# Bank_12_14_35.net
KiCad netlist of a schematic drawn in Altium Designer
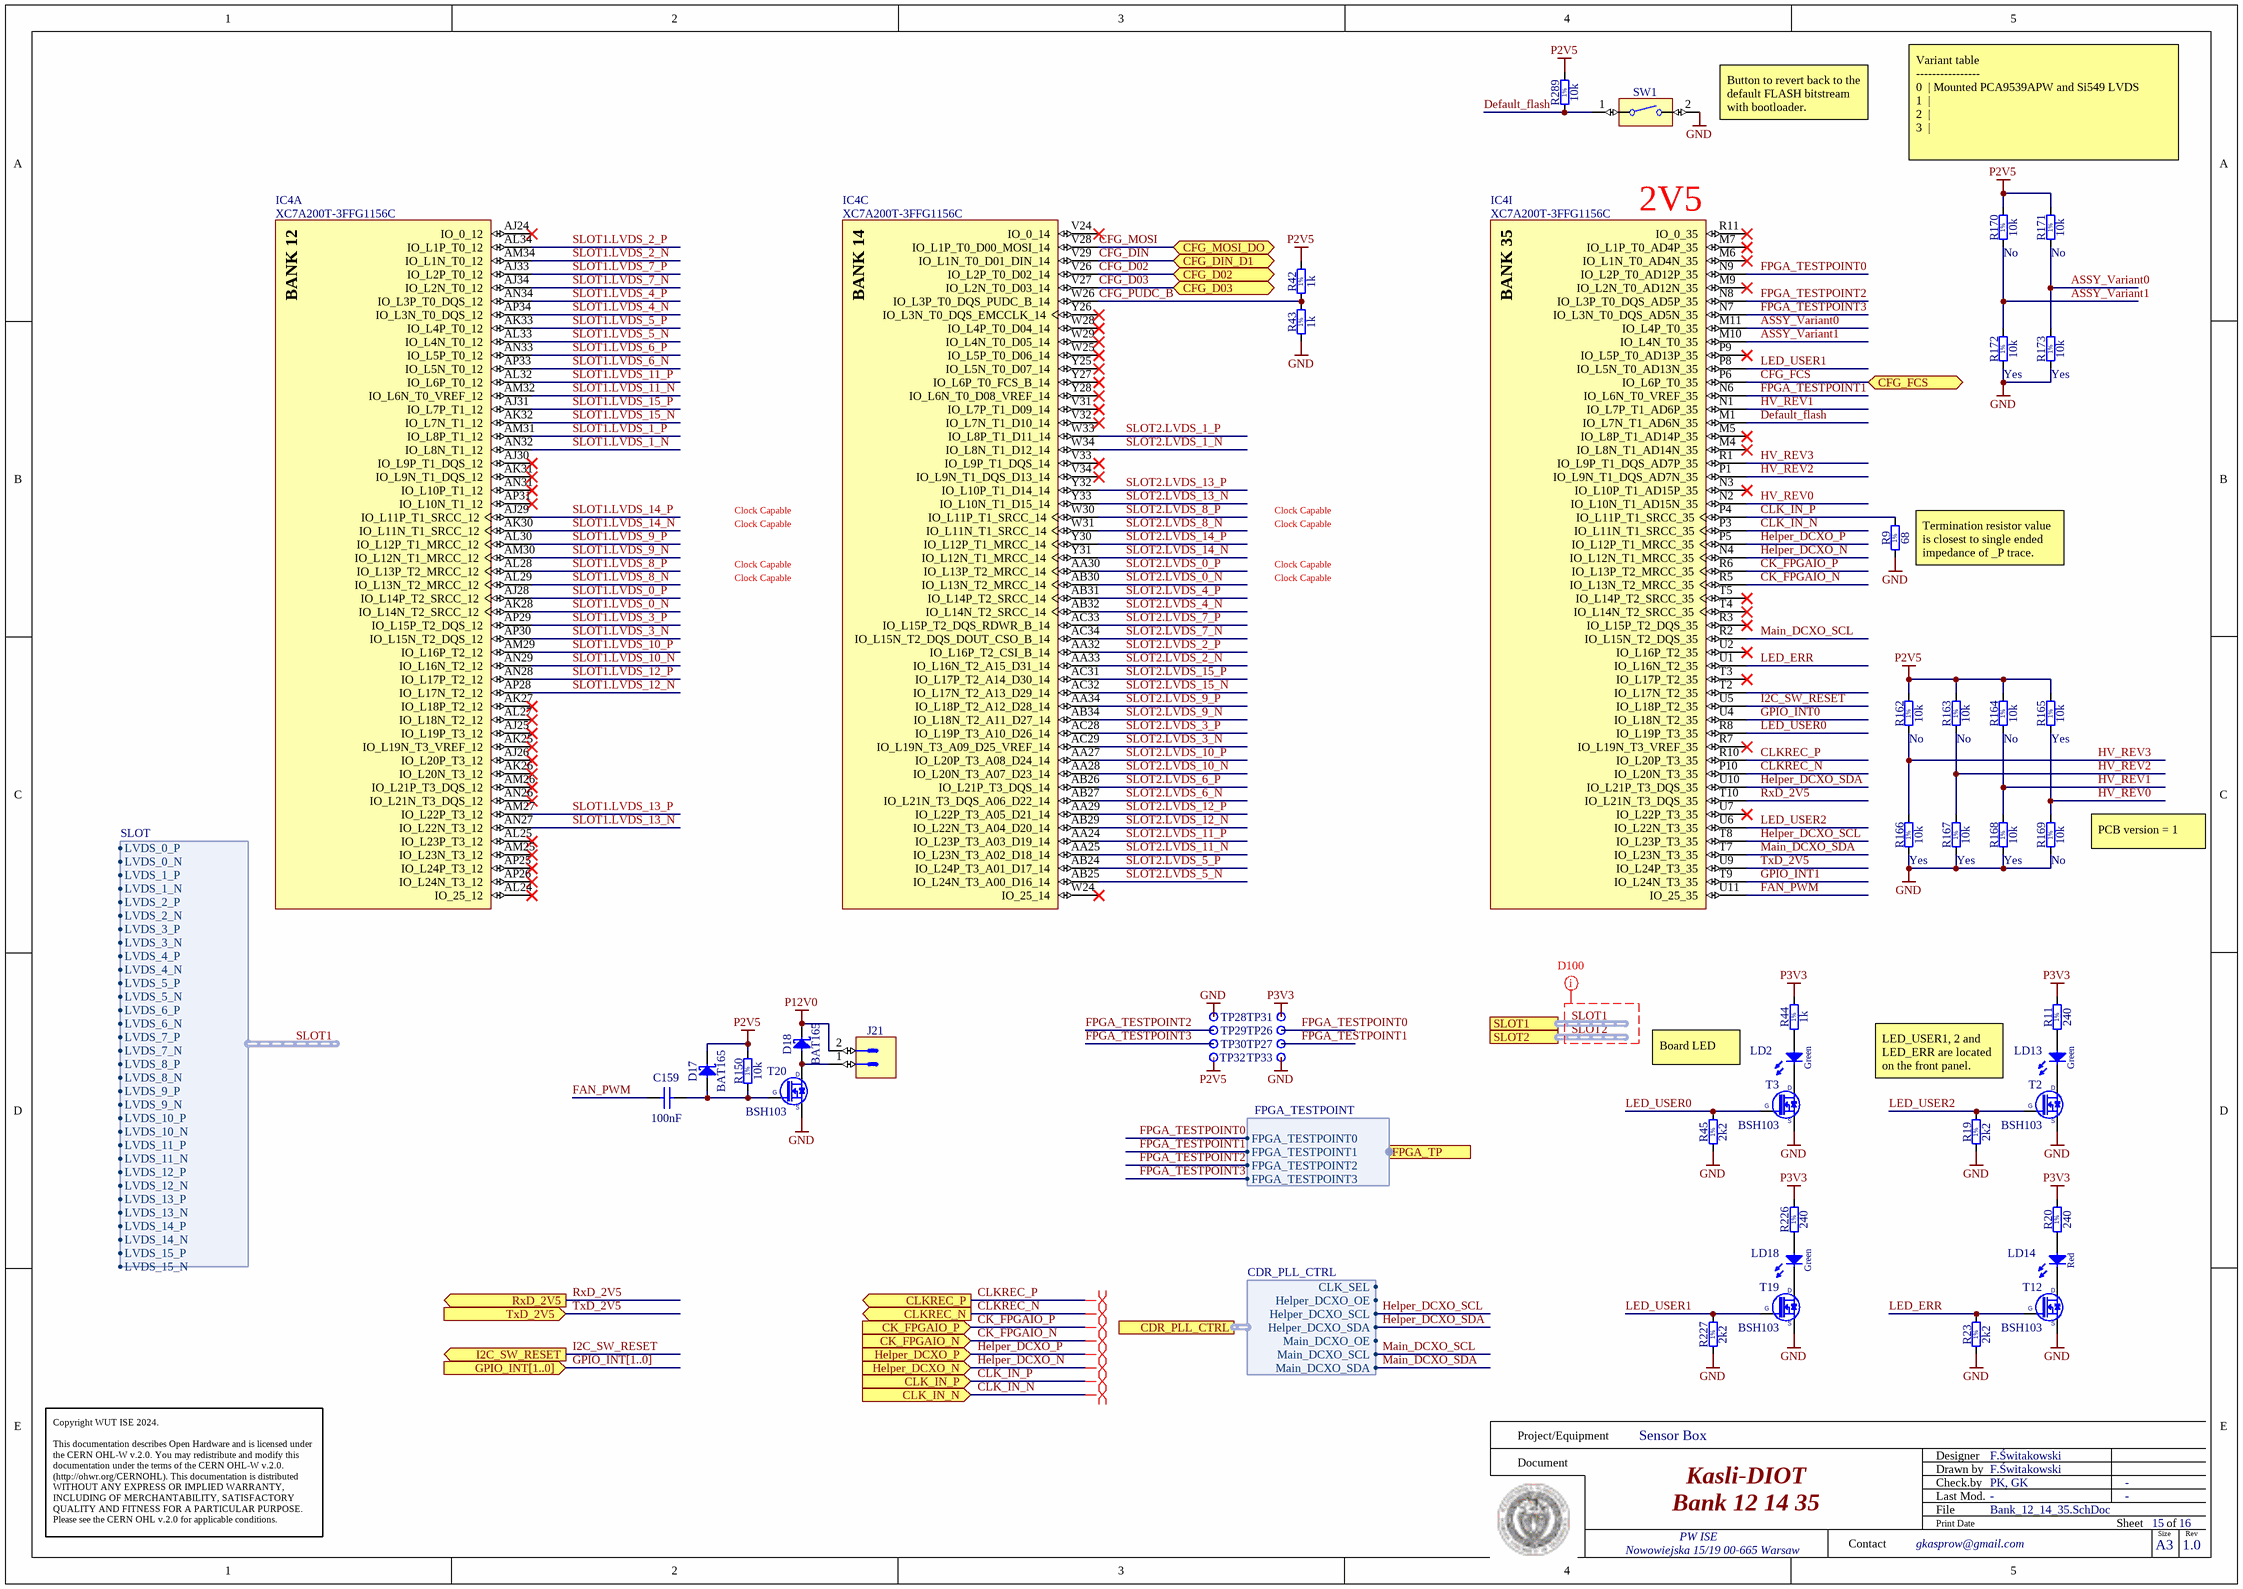
[diagram p0: Bank_12_14_35.SchDoc]

(export (version "E")
  (design (tool "Eeschema 10.0.6"))
  (components
    (comp (ref "C159")
      (value "100nF")
      (footprint "CAPC0603X33N")
      (description "Non-polarised capacitor")
      (fields
        (field (name "PART NUMBER") "CC0201_100NF_6.3V_10%_X5R")
        (field (name "VOLTAGE") "6.3V")
        (field (name "AUTHOR") "CERN DEM JLC")
      )
      (libsource (lib "Capacitors") (part "Capacitor - non polarized"))
    )
    (comp (ref "D17")
      (value "BAT165")
      (footprint "SOD2512X110N")
      (description "Schottky Diode")
      (fields
        (field (name "VOLTAGE") "40V")
        (field (name "POWER") "750mA")
        (field (name "AUTHOR") "CERN DEM JLC")
      )
      (libsource (lib "ICs And Semiconductors") (part "Diode Schottky"))
    )
    (comp (ref "D18")
      (value "BAT165")
      (footprint "SOD2512X110N")
      (description "Schottky Diode")
      (fields
        (field (name "VOLTAGE") "40V")
        (field (name "POWER") "750mA")
        (field (name "AUTHOR") "CERN DEM JLC")
      )
      (libsource (lib "ICs And Semiconductors") (part "Diode Schottky"))
    )
    (comp (ref "IC4")
      (value "XC7A200T-3FFG1156C")
      (footprint "BGA1156C100P34X34_3500X3500X310")
      (description "Artix-7 FPGA, 500 User I/Os, 16 GTP, 1156-Ball BGA, , Speed Grade 3, Commercial Grade, Pb-Free")
      (fields (field (name "MANUFACTURER") "XILINX") (field (name "AUTHOR") "CERN DEM JLC"))
      (libsource (lib "ICs And Semiconductors") (part "XC7A200T-3FFG1156C"))
    )
    (comp (ref "J21")
      (value "KK®")
      (footprint "MOLEX_22-27-2021")
      (description "Connector 2 Male")
      (fields
        (field (name "PART NUMBER") "MOLEX_22-27-2021")
        (field (name "MANUFACTURER") "MOLEX")
        (field (name "AUTHOR") "CERN DEM JLC")
      )
      (libsource (lib "Connectors") (part "Connector 2 Male"))
    )
    (comp (ref "LD2")
      (value "Green")
      (footprint "LED_KINGBRIGHT_KPH-1608CGCK")
      (description "LED Green 1C 2A")
      (fields
        (field (name "MANUFACTURER PART NUMBER") "KPH-1608CGCK")
        (field (name "PART NUMBER") "LED_KINGBRIGHT_KPH-1608CGCK")
        (field (name "AUTHOR") "CERN DEM JLC")
      )
      (libsource (lib "ICs And Semiconductors") (part "LED Green 1C 2A"))
    )
    (comp (ref "LD13")
      (value "Green")
      (footprint "LED_AVAGO_HSME-C120")
      (description "LED Green 1C 2A")
      (fields
        (field (name "MANUFACTURER PART NUMBER") "HSME-C120")
        (field (name "PART NUMBER") "LED_AVAGO_HSME-C120")
        (field (name "AUTHOR") "CERN DEM JMW")
      )
      (libsource (lib "ICs And Semiconductors") (part "LED Green 1C 2A"))
    )
    (comp (ref "LD14")
      (value "Red")
      (footprint "LED_AVAGO_HSMC-C120")
      (description "LED Red 1C 2A")
      (fields
        (field (name "MANUFACTURER PART NUMBER") "HSMC-C120")
        (field (name "PART NUMBER") "LED_AVAGO_HSMC-C120")
        (field (name "AUTHOR") "CERN DEM JMW")
      )
      (libsource (lib "ICs And Semiconductors") (part "LED Red 1C 2A"))
    )
    (comp (ref "LD18")
      (value "Green")
      (footprint "LED_AVAGO_HSME-C120")
      (description "LED Green 1C 2A")
      (fields
        (field (name "MANUFACTURER PART NUMBER") "HSME-C120")
        (field (name "PART NUMBER") "LED_AVAGO_HSME-C120")
        (field (name "AUTHOR") "CERN DEM JMW")
      )
      (libsource (lib "ICs And Semiconductors") (part "LED Green 1C 2A"))
    )
    (comp (ref "R9")
      (value "68")
      (footprint "RESC1005X40N")
      (description "Resistor - 1%")
      (fields
        (field (name "PART NUMBER") "R0402_68R_1%_0.0625W_100PPM")
        (field (name "POWER") "0.0625W")
        (field (name "AUTHOR") "CERN DEM JLC")
      )
      (libsource (lib "Resistors") (part "Resistor - 1%"))
    )
    (comp (ref "R11")
      (value "240")
      (footprint "RESC1005X40N")
      (description "Resistor - 1%")
      (fields
        (field (name "PART NUMBER") "R0402_240R_1%_0.0625W_100PPM")
        (field (name "POWER") "0.0625W")
        (field (name "AUTHOR") "CERN DEM JLC")
      )
      (libsource (lib "Resistors") (part "Resistor - 1%"))
    )
    (comp (ref "R19")
      (value "2k2")
      (footprint "RESC1005X40N")
      (description "Resistor - 1%")
      (fields
        (field (name "PART NUMBER") "R0402_2K2_1%_0.0625W_100PPM")
        (field (name "POWER") "0.0625W")
        (field (name "AUTHOR") "CERN DEM JLC")
      )
      (libsource (lib "Resistors") (part "Resistor - 1%"))
    )
    (comp (ref "R20")
      (value "240")
      (footprint "RESC1005X40N")
      (description "Resistor - 1%")
      (fields
        (field (name "PART NUMBER") "R0402_240R_1%_0.0625W_100PPM")
        (field (name "POWER") "0.0625W")
        (field (name "AUTHOR") "CERN DEM JLC")
      )
      (libsource (lib "Resistors") (part "Resistor - 1%"))
    )
    (comp (ref "R23")
      (value "2k2")
      (footprint "RESC1005X40N")
      (description "Resistor - 1%")
      (fields
        (field (name "PART NUMBER") "R0402_2K2_1%_0.0625W_100PPM")
        (field (name "POWER") "0.0625W")
        (field (name "AUTHOR") "CERN DEM JLC")
      )
      (libsource (lib "Resistors") (part "Resistor - 1%"))
    )
    (comp (ref "R42")
      (value "1k")
      (footprint "RESC1005X40N")
      (description "Resistor - 1%")
      (fields
        (field (name "PART NUMBER") "R0402_1K_1%_0.0625W_100PPM")
        (field (name "POWER") "0.0625W")
        (field (name "AUTHOR") "CERN DEM JLC")
      )
      (libsource (lib "Resistors") (part "Resistor - 1%"))
    )
    (comp (ref "R43")
      (value "1k")
      (footprint "RESC1005X40N")
      (description "Resistor - 1%")
      (fields
        (field (name "PART NUMBER") "R0402_1K_1%_0.0625W_100PPM")
        (field (name "POWER") "0.0625W")
        (field (name "AUTHOR") "CERN DEM JLC")
      )
      (libsource (lib "Resistors") (part "Resistor - 1%"))
    )
    (comp (ref "R44")
      (value "1k")
      (footprint "RESC1005X40N")
      (description "Resistor - 1%")
      (fields
        (field (name "PART NUMBER") "R0402_1K_1%_0.0625W_100PPM")
        (field (name "POWER") "0.0625W")
        (field (name "AUTHOR") "CERN DEM JLC")
      )
      (libsource (lib "Resistors") (part "Resistor - 1%"))
    )
    (comp (ref "R45")
      (value "2k2")
      (footprint "RESC1005X40N")
      (description "Resistor - 1%")
      (fields
        (field (name "PART NUMBER") "R0402_2K2_1%_0.0625W_100PPM")
        (field (name "POWER") "0.0625W")
        (field (name "AUTHOR") "CERN DEM JLC")
      )
      (libsource (lib "Resistors") (part "Resistor - 1%"))
    )
    (comp (ref "R150")
      (value "10k")
      (footprint "RESC1005X40N")
      (description "Resistor - 1%")
      (fields
        (field (name "PART NUMBER") "R0402_10K_1%_0.0625W_100PPM")
        (field (name "POWER") "0.0625W")
        (field (name "AUTHOR") "CERN DEM JLC")
      )
      (libsource (lib "Resistors") (part "Resistor - 1%"))
    )
    (comp (ref "R162")
      (value "10k")
      (footprint "RESC1005X40N")
      (description "Resistor - 1%")
      (fields
        (field (name "PART NUMBER") "R0402_10K_1%_0.0625W_100PPM")
        (field (name "POWER") "0.0625W")
        (field (name "MOUNTED") "No")
        (field (name "AUTHOR") "CERN DEM JLC")
      )
      (libsource (lib "Resistors") (part "Resistor - 1%"))
    )
    (comp (ref "R163")
      (value "10k")
      (footprint "RESC1005X40N")
      (description "Resistor - 1%")
      (fields
        (field (name "PART NUMBER") "R0402_10K_1%_0.0625W_100PPM")
        (field (name "POWER") "0.0625W")
        (field (name "MOUNTED") "No")
        (field (name "AUTHOR") "CERN DEM JLC")
      )
      (libsource (lib "Resistors") (part "Resistor - 1%"))
    )
    (comp (ref "R164")
      (value "10k")
      (footprint "RESC1005X40N")
      (description "Resistor - 1%")
      (fields
        (field (name "PART NUMBER") "R0402_10K_1%_0.0625W_100PPM")
        (field (name "POWER") "0.0625W")
        (field (name "MOUNTED") "No")
        (field (name "AUTHOR") "CERN DEM JLC")
      )
      (libsource (lib "Resistors") (part "Resistor - 1%"))
    )
    (comp (ref "R165")
      (value "10k")
      (footprint "RESC1005X40N")
      (description "Resistor - 1%")
      (fields
        (field (name "PART NUMBER") "R0402_10K_1%_0.0625W_100PPM")
        (field (name "POWER") "0.0625W")
        (field (name "MOUNTED") "Yes")
        (field (name "AUTHOR") "CERN DEM JLC")
      )
      (libsource (lib "Resistors") (part "Resistor - 1%"))
    )
    (comp (ref "R166")
      (value "10k")
      (footprint "RESC1005X40N")
      (description "Resistor - 1%")
      (fields
        (field (name "PART NUMBER") "R0402_10K_1%_0.0625W_100PPM")
        (field (name "POWER") "0.0625W")
        (field (name "MOUNTED") "Yes")
        (field (name "AUTHOR") "CERN DEM JLC")
      )
      (libsource (lib "Resistors") (part "Resistor - 1%"))
    )
    (comp (ref "R167")
      (value "10k")
      (footprint "RESC1005X40N")
      (description "Resistor - 1%")
      (fields
        (field (name "PART NUMBER") "R0402_10K_1%_0.0625W_100PPM")
        (field (name "POWER") "0.0625W")
        (field (name "MOUNTED") "Yes")
        (field (name "AUTHOR") "CERN DEM JLC")
      )
      (libsource (lib "Resistors") (part "Resistor - 1%"))
    )
    (comp (ref "R168")
      (value "10k")
      (footprint "RESC1005X40N")
      (description "Resistor - 1%")
      (fields
        (field (name "PART NUMBER") "R0402_10K_1%_0.0625W_100PPM")
        (field (name "POWER") "0.0625W")
        (field (name "MOUNTED") "Yes")
        (field (name "AUTHOR") "CERN DEM JLC")
      )
      (libsource (lib "Resistors") (part "Resistor - 1%"))
    )
    (comp (ref "R169")
      (value "10k")
      (footprint "RESC1005X40N")
      (description "Resistor - 1%")
      (fields
        (field (name "PART NUMBER") "R0402_10K_1%_0.0625W_100PPM")
        (field (name "POWER") "0.0625W")
        (field (name "MOUNTED") "No")
        (field (name "AUTHOR") "CERN DEM JLC")
      )
      (libsource (lib "Resistors") (part "Resistor - 1%"))
    )
    (comp (ref "R170")
      (value "10k")
      (footprint "RESC1005X40N")
      (description "Resistor - 1%")
      (fields
        (field (name "PART NUMBER") "R0402_10K_1%_0.0625W_100PPM")
        (field (name "POWER") "0.0625W")
        (field (name "MOUNTED") "No")
        (field (name "AUTHOR") "CERN DEM JLC")
      )
      (libsource (lib "Resistors") (part "Resistor - 1%"))
    )
    (comp (ref "R171")
      (value "10k")
      (footprint "RESC1005X40N")
      (description "Resistor - 1%")
      (fields
        (field (name "PART NUMBER") "R0402_10K_1%_0.0625W_100PPM")
        (field (name "POWER") "0.0625W")
        (field (name "MOUNTED") "No")
        (field (name "AUTHOR") "CERN DEM JLC")
      )
      (libsource (lib "Resistors") (part "Resistor - 1%"))
    )
    (comp (ref "R172")
      (value "10k")
      (footprint "RESC1005X40N")
      (description "Resistor - 1%")
      (fields
        (field (name "PART NUMBER") "R0402_10K_1%_0.0625W_100PPM")
        (field (name "POWER") "0.0625W")
        (field (name "MOUNTED") "Yes")
        (field (name "AUTHOR") "CERN DEM JLC")
      )
      (libsource (lib "Resistors") (part "Resistor - 1%"))
    )
    (comp (ref "R173")
      (value "10k")
      (footprint "RESC1005X40N")
      (description "Resistor - 1%")
      (fields
        (field (name "PART NUMBER") "R0402_10K_1%_0.0625W_100PPM")
        (field (name "POWER") "0.0625W")
        (field (name "MOUNTED") "Yes")
        (field (name "AUTHOR") "CERN DEM JLC")
      )
      (libsource (lib "Resistors") (part "Resistor - 1%"))
    )
    (comp (ref "R226")
      (value "240")
      (footprint "RESC1005X40N")
      (description "Resistor - 1%")
      (fields
        (field (name "PART NUMBER") "R0402_240R_1%_0.0625W_100PPM")
        (field (name "POWER") "0.0625W")
        (field (name "AUTHOR") "CERN DEM JLC")
      )
      (libsource (lib "Resistors") (part "Resistor - 1%"))
    )
    (comp (ref "R227")
      (value "2k2")
      (footprint "RESC1005X40N")
      (description "Resistor - 1%")
      (fields
        (field (name "PART NUMBER") "R0402_2K2_1%_0.0625W_100PPM")
        (field (name "POWER") "0.0625W")
        (field (name "AUTHOR") "CERN DEM JLC")
      )
      (libsource (lib "Resistors") (part "Resistor - 1%"))
    )
    (comp (ref "R289")
      (value "10k")
      (footprint "RESC1005X40N")
      (description "Resistor - 1%")
      (fields
        (field (name "PART NUMBER") "R0402_10K_1%_0.0625W_100PPM")
        (field (name "POWER") "0.0625W")
        (field (name "AUTHOR") "CERN DEM JLC")
      )
      (libsource (lib "Resistors") (part "Resistor - 1%"))
    )
    (comp (ref "SW1")
      (value "Switch")
      (footprint "SW_OMRON_B3U-3000PM")
      (description "1 Ways SPST DIP Switch")
      (fields
        (field (name "PART NUMBER") "SW_OMRON_B3U-3000PM")
        (field (name "MANUFACTURER") "OMRON")
        (field (name "AUTHOR") "CERN DEM HF")
      )
      (libsource (lib "Eletro-mechanical") (part "SW 1x SPST DIP Switch"))
    )
    (comp (ref "T2")
      (value "BSH103")
      (footprint "SOT95P230X110-3N")
      (description "N-CHANNEL MOSFET WITH DIODE")
      (fields (field (name "MANUFACTURER") "NEXPERIA") (field (name "AUTHOR") "CERN DEM JLC"))
      (libsource (lib "ICs And Semiconductors") (part "N-MOSFET-D 1G 2S 3D"))
    )
    (comp (ref "T3")
      (value "BSH103")
      (footprint "SOT95P230X110-3N")
      (description "N-CHANNEL MOSFET WITH DIODE")
      (fields (field (name "MANUFACTURER") "NEXPERIA") (field (name "AUTHOR") "CERN DEM JLC"))
      (libsource (lib "ICs And Semiconductors") (part "N-MOSFET-D 1G 2S 3D"))
    )
    (comp (ref "T12")
      (value "BSH103")
      (footprint "SOT95P230X110-3N")
      (description "N-CHANNEL MOSFET WITH DIODE")
      (fields (field (name "MANUFACTURER") "NEXPERIA") (field (name "AUTHOR") "CERN DEM JLC"))
      (libsource (lib "ICs And Semiconductors") (part "N-MOSFET-D 1G 2S 3D"))
    )
    (comp (ref "T19")
      (value "BSH103")
      (footprint "SOT95P230X110-3N")
      (description "N-CHANNEL MOSFET WITH DIODE")
      (fields (field (name "MANUFACTURER") "NEXPERIA") (field (name "AUTHOR") "CERN DEM JLC"))
      (libsource (lib "ICs And Semiconductors") (part "N-MOSFET-D 1G 2S 3D"))
    )
    (comp (ref "T20")
      (value "BSH103")
      (footprint "SOT95P230X110-3N")
      (description "N-CHANNEL MOSFET WITH DIODE")
      (fields (field (name "MANUFACTURER") "NEXPERIA") (field (name "AUTHOR") "CERN DEM JLC"))
      (libsource (lib "ICs And Semiconductors") (part "N-MOSFET-D 1G 2S 3D"))
    )
    (comp (ref "TP26")
      (value "Plated Hole")
      (footprint "c170h100")
      (description "Single Terminal Socket")
      (fields (field (name "PART NUMBER") "PLATED_HOLE1.0_PAD1.7") (field (name "AUTHOR") "CERN DEM JLC"))
      (libsource (lib "Eletro-mechanical") (part "Single Terminal Socket"))
    )
    (comp (ref "TP27")
      (value "Plated Hole")
      (footprint "c170h100")
      (description "Single Terminal Socket")
      (fields (field (name "PART NUMBER") "PLATED_HOLE1.0_PAD1.7") (field (name "AUTHOR") "CERN DEM JLC"))
      (libsource (lib "Eletro-mechanical") (part "Single Terminal Socket"))
    )
    (comp (ref "TP28")
      (value "Plated Hole")
      (footprint "c170h100")
      (description "Single Terminal Socket")
      (fields (field (name "PART NUMBER") "PLATED_HOLE1.0_PAD1.7") (field (name "AUTHOR") "CERN DEM JLC"))
      (libsource (lib "Eletro-mechanical") (part "Single Terminal Socket"))
    )
    (comp (ref "TP29")
      (value "Plated Hole")
      (footprint "c170h100")
      (description "Single Terminal Socket")
      (fields (field (name "PART NUMBER") "PLATED_HOLE1.0_PAD1.7") (field (name "AUTHOR") "CERN DEM JLC"))
      (libsource (lib "Eletro-mechanical") (part "Single Terminal Socket"))
    )
    (comp (ref "TP30")
      (value "Plated Hole")
      (footprint "c170h100")
      (description "Single Terminal Socket")
      (fields (field (name "PART NUMBER") "PLATED_HOLE1.0_PAD1.7") (field (name "AUTHOR") "CERN DEM JLC"))
      (libsource (lib "Eletro-mechanical") (part "Single Terminal Socket"))
    )
    (comp (ref "TP31")
      (value "Plated Hole")
      (footprint "c170h100")
      (description "Single Terminal Socket")
      (fields (field (name "PART NUMBER") "PLATED_HOLE1.0_PAD1.7") (field (name "AUTHOR") "CERN DEM JLC"))
      (libsource (lib "Eletro-mechanical") (part "Single Terminal Socket"))
    )
    (comp (ref "TP32")
      (value "Plated Hole")
      (footprint "c170h100")
      (description "Single Terminal Socket")
      (fields (field (name "PART NUMBER") "PLATED_HOLE1.0_PAD1.7") (field (name "AUTHOR") "CERN DEM JLC"))
      (libsource (lib "Eletro-mechanical") (part "Single Terminal Socket"))
    )
    (comp (ref "TP33")
      (value "Plated Hole")
      (footprint "c170h100")
      (description "Single Terminal Socket")
      (fields (field (name "PART NUMBER") "PLATED_HOLE1.0_PAD1.7") (field (name "AUTHOR") "CERN DEM JLC"))
      (libsource (lib "Eletro-mechanical") (part "Single Terminal Socket"))
    )
  )
  (nets
    (net (code "6") (name "/ASSY_Variant0") (class "Default")
      (node (ref "IC4") (pin "M11") (pinfunction "IO_L4P_T0_35_M11") (pintype "bidirectional"))
      (node (ref "R171") (pin "1") (pinfunction "1_1") (pintype "passive"))
      (node (ref "R173") (pin "2") (pinfunction "2_2") (pintype "passive"))
    )
    (net (code "7") (name "/ASSY_Variant1") (class "Default")
      (node (ref "IC4") (pin "M10") (pinfunction "IO_L4N_T0_35_M10") (pintype "bidirectional"))
      (node (ref "R170") (pin "1") (pinfunction "1_1") (pintype "passive"))
      (node (ref "R172") (pin "2") (pinfunction "2_2") (pintype "passive"))
    )
    (net (code "8") (name "/CFG_D02") (class "Default")
      (node (ref "IC4") (pin "V26") (pinfunction "IO_L2P_T0_D02_14_V26") (pintype "bidirectional"))
    )
    (net (code "9") (name "/CFG_D03") (class "Default")
      (node (ref "IC4") (pin "V27") (pinfunction "IO_L2N_T0_D03_14_V27") (pintype "bidirectional"))
    )
    (net (code "10") (name "/CFG_DIN") (class "Default")
      (node (ref "IC4") (pin "V29") (pinfunction "IO_L1N_T0_D01_DIN_14_V29") (pintype "bidirectional"))
    )
    (net (code "11") (name "/CFG_FCS") (class "Default")
      (node (ref "IC4") (pin "P6") (pinfunction "IO_L6P_T0_35_P6") (pintype "bidirectional"))
    )
    (net (code "12") (name "/CFG_MOSI") (class "Default")
      (node (ref "IC4") (pin "V28") (pinfunction "IO_L1P_T0_D00_MOSI_14_V28") (pintype "bidirectional"))
    )
    (net (code "13") (name "/CFG_PUDC_B") (class "Default")
      (node (ref "IC4") (pin "W26") (pinfunction "IO_L3P_T0_DQS_PUDC_B_14_W26") (pintype "bidirectional"))
      (node (ref "R42") (pin "1") (pinfunction "1_1") (pintype "passive"))
      (node (ref "R43") (pin "2") (pinfunction "2_2") (pintype "passive"))
    )
    (net (code "14") (name "/CK_FPGAIO_N") (class "Default")
      (node (ref "IC4") (pin "R5") (pinfunction "IO_L13N_T2_MRCC_35_R5") (pintype "bidirectional"))
    )
    (net (code "15") (name "/CK_FPGAIO_P") (class "Default")
      (node (ref "IC4") (pin "R6") (pinfunction "IO_L13P_T2_MRCC_35_R6") (pintype "bidirectional"))
    )
    (net (code "16") (name "/CLKREC_N") (class "Default")
      (node (ref "IC4") (pin "P10") (pinfunction "IO_L20N_T3_35_P10") (pintype "bidirectional"))
    )
    (net (code "17") (name "/CLKREC_P") (class "Default")
      (node (ref "IC4") (pin "R10") (pinfunction "IO_L20P_T3_35_R10") (pintype "bidirectional"))
    )
    (net (code "18") (name "/CLK_IN_N") (class "Default")
      (node (ref "IC4") (pin "P3") (pinfunction "IO_L11N_T1_SRCC_35_P3") (pintype "bidirectional"))
    )
    (net (code "19") (name "/CLK_IN_P") (class "Default")
      (node (ref "IC4") (pin "P4") (pinfunction "IO_L11P_T1_SRCC_35_P4") (pintype "bidirectional"))
      (node (ref "R9") (pin "2") (pinfunction "2_2") (pintype "passive"))
    )
    (net (code "20") (name "/Default_flash") (class "Default")
      (node (ref "IC4") (pin "M1") (pinfunction "IO_L7N_T1_AD6N_35_M1") (pintype "bidirectional"))
      (node (ref "R289") (pin "1") (pinfunction "1_1") (pintype "passive"))
      (node (ref "SW1") (pin "1") (pinfunction "1_1") (pintype "bidirectional"))
    )
    (net (code "21") (name "/FAN_PWM") (class "Default")
      (node (ref "C159") (pin "2") (pinfunction "2_2") (pintype "passive"))
      (node (ref "IC4") (pin "U11") (pinfunction "IO_25_35_U11") (pintype "bidirectional"))
    )
    (net (code "22") (name "/FPGA_TESTPOINT0") (class "Default")
      (node (ref "IC4") (pin "N9") (pinfunction "IO_L2P_T0_AD12P_35_N9") (pintype "bidirectional"))
      (node (ref "TP26") (pin "1") (pinfunction "1_1") (pintype "bidirectional"))
    )
    (net (code "23") (name "/FPGA_TESTPOINT1") (class "Default")
      (node (ref "IC4") (pin "N6") (pinfunction "IO_L6N_T0_VREF_35_N6") (pintype "bidirectional"))
      (node (ref "TP27") (pin "1") (pinfunction "1_1") (pintype "bidirectional"))
    )
    (net (code "24") (name "/FPGA_TESTPOINT2") (class "Default")
      (node (ref "IC4") (pin "N8") (pinfunction "IO_L3P_T0_DQS_AD5P_35_N8") (pintype "bidirectional"))
      (node (ref "TP29") (pin "1") (pinfunction "1_1") (pintype "bidirectional"))
    )
    (net (code "25") (name "/FPGA_TESTPOINT3") (class "Default")
      (node (ref "IC4") (pin "N7") (pinfunction "IO_L3N_T0_DQS_AD5N_35_N7") (pintype "bidirectional"))
      (node (ref "TP30") (pin "1") (pinfunction "1_1") (pintype "bidirectional"))
    )
    (net (code "26") (name "/GPIO_INT0") (class "Default")
      (node (ref "IC4") (pin "U4") (pinfunction "IO_L18N_T2_35_U4") (pintype "bidirectional"))
    )
    (net (code "27") (name "/GPIO_INT1") (class "Default")
      (node (ref "IC4") (pin "T9") (pinfunction "IO_L24N_T3_35_T9") (pintype "bidirectional"))
    )
    (net (code "29") (name "/HV_REV0") (class "Default")
      (node (ref "IC4") (pin "N2") (pinfunction "IO_L10N_T1_AD15N_35_N2") (pintype "bidirectional"))
      (node (ref "R165") (pin "1") (pinfunction "1_1") (pintype "passive"))
      (node (ref "R169") (pin "2") (pinfunction "2_2") (pintype "passive"))
    )
    (net (code "30") (name "/HV_REV1") (class "Default")
      (node (ref "IC4") (pin "N1") (pinfunction "IO_L7P_T1_AD6P_35_N1") (pintype "bidirectional"))
      (node (ref "R164") (pin "1") (pinfunction "1_1") (pintype "passive"))
      (node (ref "R168") (pin "2") (pinfunction "2_2") (pintype "passive"))
    )
    (net (code "31") (name "/HV_REV2") (class "Default")
      (node (ref "IC4") (pin "P1") (pinfunction "IO_L9N_T1_DQS_AD7N_35_P1") (pintype "bidirectional"))
      (node (ref "R163") (pin "1") (pinfunction "1_1") (pintype "passive"))
      (node (ref "R167") (pin "2") (pinfunction "2_2") (pintype "passive"))
    )
    (net (code "32") (name "/HV_REV3") (class "Default")
      (node (ref "IC4") (pin "R1") (pinfunction "IO_L9P_T1_DQS_AD7P_35_R1") (pintype "bidirectional"))
      (node (ref "R162") (pin "1") (pinfunction "1_1") (pintype "passive"))
      (node (ref "R166") (pin "2") (pinfunction "2_2") (pintype "passive"))
    )
    (net (code "33") (name "/Helper_DCXO_N") (class "Default")
      (node (ref "IC4") (pin "N4") (pinfunction "IO_L12N_T1_MRCC_35_N4") (pintype "bidirectional"))
    )
    (net (code "34") (name "/Helper_DCXO_P") (class "Default")
      (node (ref "IC4") (pin "P5") (pinfunction "IO_L12P_T1_MRCC_35_P5") (pintype "bidirectional"))
    )
    (net (code "35") (name "/Helper_DCXO_SCL") (class "Default")
      (node (ref "IC4") (pin "T8") (pinfunction "IO_L23P_T3_35_T8") (pintype "bidirectional"))
    )
    (net (code "36") (name "/Helper_DCXO_SDA") (class "Default")
      (node (ref "IC4") (pin "U10") (pinfunction "IO_L21P_T3_DQS_35_U10") (pintype "bidirectional"))
    )
    (net (code "37") (name "/I2C_SW_RESET") (class "Default")
      (node (ref "IC4") (pin "U5") (pinfunction "IO_L18P_T2_35_U5") (pintype "bidirectional"))
    )
    (net (code "38") (name "/LED_ERR") (class "Default")
      (node (ref "IC4") (pin "U1") (pinfunction "IO_L16N_T2_35_U1") (pintype "bidirectional"))
      (node (ref "R23") (pin "2") (pinfunction "2_2") (pintype "passive"))
      (node (ref "T12") (pin "1") (pinfunction "G_1") (pintype "passive"))
    )
    (net (code "39") (name "/LED_USER0") (class "Default")
      (node (ref "IC4") (pin "R8") (pinfunction "IO_L19P_T3_35_R8") (pintype "bidirectional"))
      (node (ref "R45") (pin "2") (pinfunction "2_2") (pintype "passive"))
      (node (ref "T3") (pin "1") (pinfunction "G_1") (pintype "passive"))
    )
    (net (code "40") (name "/LED_USER1") (class "Default")
      (node (ref "IC4") (pin "P8") (pinfunction "IO_L5N_T0_AD13N_35_P8") (pintype "bidirectional"))
      (node (ref "R227") (pin "2") (pinfunction "2_2") (pintype "passive"))
      (node (ref "T19") (pin "1") (pinfunction "G_1") (pintype "passive"))
    )
    (net (code "41") (name "/LED_USER2") (class "Default")
      (node (ref "IC4") (pin "U6") (pinfunction "IO_L22N_T3_35_U6") (pintype "bidirectional"))
      (node (ref "R19") (pin "2") (pinfunction "2_2") (pintype "passive"))
      (node (ref "T2") (pin "1") (pinfunction "G_1") (pintype "passive"))
    )
    (net (code "42") (name "/Main_DCXO_SCL") (class "Default")
      (node (ref "IC4") (pin "R2") (pinfunction "IO_L15N_T2_DQS_35_R2") (pintype "bidirectional"))
    )
    (net (code "43") (name "/Main_DCXO_SDA") (class "Default")
      (node (ref "IC4") (pin "T7") (pinfunction "IO_L23N_T3_35_T7") (pintype "bidirectional"))
    )
    (net (code "44") (name "/RxD_2V5") (class "Default")
      (node (ref "IC4") (pin "T10") (pinfunction "IO_L21N_T3_DQS_35_T10") (pintype "bidirectional"))
    )
    (net (code "45") (name "/SLOT1.LVDS_0_N") (class "Default")
      (node (ref "IC4") (pin "AK28") (pinfunction "IO_L14N_T2_SRCC_12_AK28") (pintype "bidirectional"))
    )
    (net (code "46") (name "/SLOT1.LVDS_0_P") (class "Default")
      (node (ref "IC4") (pin "AJ28") (pinfunction "IO_L14P_T2_SRCC_12_AJ28") (pintype "bidirectional"))
    )
    (net (code "47") (name "/SLOT1.LVDS_1_N") (class "Default")
      (node (ref "IC4") (pin "AN32") (pinfunction "IO_L8N_T1_12_AN32") (pintype "bidirectional"))
    )
    (net (code "48") (name "/SLOT1.LVDS_1_P") (class "Default")
      (node (ref "IC4") (pin "AM31") (pinfunction "IO_L8P_T1_12_AM31") (pintype "bidirectional"))
    )
    (net (code "49") (name "/SLOT1.LVDS_2_N") (class "Default")
      (node (ref "IC4") (pin "AM34") (pinfunction "IO_L1N_T0_12_AM34") (pintype "bidirectional"))
    )
    (net (code "50") (name "/SLOT1.LVDS_2_P") (class "Default")
      (node (ref "IC4") (pin "AL34") (pinfunction "IO_L1P_T0_12_AL34") (pintype "bidirectional"))
    )
    (net (code "51") (name "/SLOT1.LVDS_3_N") (class "Default")
      (node (ref "IC4") (pin "AP30") (pinfunction "IO_L15N_T2_DQS_12_AP30") (pintype "bidirectional"))
    )
    (net (code "52") (name "/SLOT1.LVDS_3_P") (class "Default")
      (node (ref "IC4") (pin "AP29") (pinfunction "IO_L15P_T2_DQS_12_AP29") (pintype "bidirectional"))
    )
    (net (code "53") (name "/SLOT1.LVDS_4_N") (class "Default")
      (node (ref "IC4") (pin "AP34") (pinfunction "IO_L3N_T0_DQS_12_AP34") (pintype "bidirectional"))
    )
    (net (code "54") (name "/SLOT1.LVDS_4_P") (class "Default")
      (node (ref "IC4") (pin "AN34") (pinfunction "IO_L3P_T0_DQS_12_AN34") (pintype "bidirectional"))
    )
    (net (code "55") (name "/SLOT1.LVDS_5_N") (class "Default")
      (node (ref "IC4") (pin "AL33") (pinfunction "IO_L4N_T0_12_AL33") (pintype "bidirectional"))
    )
    (net (code "56") (name "/SLOT1.LVDS_5_P") (class "Default")
      (node (ref "IC4") (pin "AK33") (pinfunction "IO_L4P_T0_12_AK33") (pintype "bidirectional"))
    )
    (net (code "57") (name "/SLOT1.LVDS_6_N") (class "Default")
      (node (ref "IC4") (pin "AP33") (pinfunction "IO_L5N_T0_12_AP33") (pintype "bidirectional"))
    )
    (net (code "58") (name "/SLOT1.LVDS_6_P") (class "Default")
      (node (ref "IC4") (pin "AN33") (pinfunction "IO_L5P_T0_12_AN33") (pintype "bidirectional"))
    )
    (net (code "59") (name "/SLOT1.LVDS_7_N") (class "Default")
      (node (ref "IC4") (pin "AJ34") (pinfunction "IO_L2N_T0_12_AJ34") (pintype "bidirectional"))
    )
    (net (code "60") (name "/SLOT1.LVDS_7_P") (class "Default")
      (node (ref "IC4") (pin "AJ33") (pinfunction "IO_L2P_T0_12_AJ33") (pintype "bidirectional"))
    )
    (net (code "61") (name "/SLOT1.LVDS_8_N") (class "Default")
      (node (ref "IC4") (pin "AL29") (pinfunction "IO_L13N_T2_MRCC_12_AL29") (pintype "bidirectional"))
    )
    (net (code "62") (name "/SLOT1.LVDS_8_P") (class "Default")
      (node (ref "IC4") (pin "AL28") (pinfunction "IO_L13P_T2_MRCC_12_AL28") (pintype "bidirectional"))
    )
    (net (code "63") (name "/SLOT1.LVDS_9_N") (class "Default")
      (node (ref "IC4") (pin "AM30") (pinfunction "IO_L12N_T1_MRCC_12_AM30") (pintype "bidirectional"))
    )
    (net (code "64") (name "/SLOT1.LVDS_9_P") (class "Default")
      (node (ref "IC4") (pin "AL30") (pinfunction "IO_L12P_T1_MRCC_12_AL30") (pintype "bidirectional"))
    )
    (net (code "65") (name "/SLOT1.LVDS_10_N") (class "Default")
      (node (ref "IC4") (pin "AN29") (pinfunction "IO_L16N_T2_12_AN29") (pintype "bidirectional"))
    )
    (net (code "66") (name "/SLOT1.LVDS_10_P") (class "Default")
      (node (ref "IC4") (pin "AM29") (pinfunction "IO_L16P_T2_12_AM29") (pintype "bidirectional"))
    )
    (net (code "67") (name "/SLOT1.LVDS_11_N") (class "Default")
      (node (ref "IC4") (pin "AM32") (pinfunction "IO_L6N_T0_VREF_12_AM32") (pintype "bidirectional"))
    )
    (net (code "68") (name "/SLOT1.LVDS_11_P") (class "Default")
      (node (ref "IC4") (pin "AL32") (pinfunction "IO_L6P_T0_12_AL32") (pintype "bidirectional"))
    )
    (net (code "69") (name "/SLOT1.LVDS_12_N") (class "Default")
      (node (ref "IC4") (pin "AP28") (pinfunction "IO_L17N_T2_12_AP28") (pintype "bidirectional"))
    )
    (net (code "70") (name "/SLOT1.LVDS_12_P") (class "Default")
      (node (ref "IC4") (pin "AN28") (pinfunction "IO_L17P_T2_12_AN28") (pintype "bidirectional"))
    )
    (net (code "71") (name "/SLOT1.LVDS_13_N") (class "Default")
      (node (ref "IC4") (pin "AN27") (pinfunction "IO_L22N_T3_12_AN27") (pintype "bidirectional"))
    )
    (net (code "72") (name "/SLOT1.LVDS_13_P") (class "Default")
      (node (ref "IC4") (pin "AM27") (pinfunction "IO_L22P_T3_12_AM27") (pintype "bidirectional"))
    )
    (net (code "73") (name "/SLOT1.LVDS_14_N") (class "Default")
      (node (ref "IC4") (pin "AK30") (pinfunction "IO_L11N_T1_SRCC_12_AK30") (pintype "bidirectional"))
    )
    (net (code "74") (name "/SLOT1.LVDS_14_P") (class "Default")
      (node (ref "IC4") (pin "AJ29") (pinfunction "IO_L11P_T1_SRCC_12_AJ29") (pintype "bidirectional"))
    )
    (net (code "75") (name "/SLOT1.LVDS_15_N") (class "Default")
      (node (ref "IC4") (pin "AK32") (pinfunction "IO_L7N_T1_12_AK32") (pintype "bidirectional"))
    )
    (net (code "76") (name "/SLOT1.LVDS_15_P") (class "Default")
      (node (ref "IC4") (pin "AJ31") (pinfunction "IO_L7P_T1_12_AJ31") (pintype "bidirectional"))
    )
    (net (code "78") (name "/SLOT2.LVDS_0_N") (class "Default")
      (node (ref "IC4") (pin "AB30") (pinfunction "IO_L13N_T2_MRCC_14_AB30") (pintype "bidirectional"))
    )
    (net (code "79") (name "/SLOT2.LVDS_0_P") (class "Default")
      (node (ref "IC4") (pin "AA30") (pinfunction "IO_L13P_T2_MRCC_14_AA30") (pintype "bidirectional"))
    )
    (net (code "80") (name "/SLOT2.LVDS_1_N") (class "Default")
      (node (ref "IC4") (pin "W34") (pinfunction "IO_L8N_T1_D12_14_W34") (pintype "bidirectional"))
    )
    (net (code "81") (name "/SLOT2.LVDS_1_P") (class "Default")
      (node (ref "IC4") (pin "W33") (pinfunction "IO_L8P_T1_D11_14_W33") (pintype "bidirectional"))
    )
    (net (code "82") (name "/SLOT2.LVDS_2_N") (class "Default")
      (node (ref "IC4") (pin "AA33") (pinfunction "IO_L16N_T2_A15_D31_14_AA33") (pintype "bidirectional"))
    )
    (net (code "83") (name "/SLOT2.LVDS_2_P") (class "Default")
      (node (ref "IC4") (pin "AA32") (pinfunction "IO_L16P_T2_CSI_B_14_AA32") (pintype "bidirectional"))
    )
    (net (code "84") (name "/SLOT2.LVDS_3_N") (class "Default")
      (node (ref "IC4") (pin "AC29") (pinfunction "IO_L19N_T3_A09_D25_VREF_14_AC29") (pintype "bidirectional"))
    )
    (net (code "85") (name "/SLOT2.LVDS_3_P") (class "Default")
      (node (ref "IC4") (pin "AC28") (pinfunction "IO_L19P_T3_A10_D26_14_AC28") (pintype "bidirectional"))
    )
    (net (code "86") (name "/SLOT2.LVDS_4_N") (class "Default")
      (node (ref "IC4") (pin "AB32") (pinfunction "IO_L14N_T2_SRCC_14_AB32") (pintype "bidirectional"))
    )
    (net (code "87") (name "/SLOT2.LVDS_4_P") (class "Default")
      (node (ref "IC4") (pin "AB31") (pinfunction "IO_L14P_T2_SRCC_14_AB31") (pintype "bidirectional"))
    )
    (net (code "88") (name "/SLOT2.LVDS_5_N") (class "Default")
      (node (ref "IC4") (pin "AB25") (pinfunction "IO_L24N_T3_A00_D16_14_AB25") (pintype "bidirectional"))
    )
    (net (code "89") (name "/SLOT2.LVDS_5_P") (class "Default")
      (node (ref "IC4") (pin "AB24") (pinfunction "IO_L24P_T3_A01_D17_14_AB24") (pintype "bidirectional"))
    )
    (net (code "90") (name "/SLOT2.LVDS_6_N") (class "Default")
      (node (ref "IC4") (pin "AB27") (pinfunction "IO_L21N_T3_DQS_A06_D22_14_AB27") (pintype "bidirectional"))
    )
    (net (code "91") (name "/SLOT2.LVDS_6_P") (class "Default")
      (node (ref "IC4") (pin "AB26") (pinfunction "IO_L21P_T3_DQS_14_AB26") (pintype "bidirectional"))
    )
    (net (code "92") (name "/SLOT2.LVDS_7_N") (class "Default")
      (node (ref "IC4") (pin "AC34") (pinfunction "IO_L15N_T2_DQS_DOUT_CSO_B_14_AC34") (pintype "bidirectional"))
    )
    (net (code "93") (name "/SLOT2.LVDS_7_P") (class "Default")
      (node (ref "IC4") (pin "AC33") (pinfunction "IO_L15P_T2_DQS_RDWR_B_14_AC33") (pintype "bidirectional"))
    )
    (net (code "94") (name "/SLOT2.LVDS_8_N") (class "Default")
      (node (ref "IC4") (pin "W31") (pinfunction "IO_L11N_T1_SRCC_14_W31") (pintype "bidirectional"))
    )
    (net (code "95") (name "/SLOT2.LVDS_8_P") (class "Default")
      (node (ref "IC4") (pin "W30") (pinfunction "IO_L11P_T1_SRCC_14_W30") (pintype "bidirectional"))
    )
    (net (code "96") (name "/SLOT2.LVDS_9_N") (class "Default")
      (node (ref "IC4") (pin "AB34") (pinfunction "IO_L18N_T2_A11_D27_14_AB34") (pintype "bidirectional"))
    )
    (net (code "97") (name "/SLOT2.LVDS_9_P") (class "Default")
      (node (ref "IC4") (pin "AA34") (pinfunction "IO_L18P_T2_A12_D28_14_AA34") (pintype "bidirectional"))
    )
    (net (code "98") (name "/SLOT2.LVDS_10_N") (class "Default")
      (node (ref "IC4") (pin "AA28") (pinfunction "IO_L20N_T3_A07_D23_14_AA28") (pintype "bidirectional"))
    )
    (net (code "99") (name "/SLOT2.LVDS_10_P") (class "Default")
      (node (ref "IC4") (pin "AA27") (pinfunction "IO_L20P_T3_A08_D24_14_AA27") (pintype "bidirectional"))
    )
    (net (code "100") (name "/SLOT2.LVDS_11_N") (class "Default")
      (node (ref "IC4") (pin "AA25") (pinfunction "IO_L23N_T3_A02_D18_14_AA25") (pintype "bidirectional"))
    )
    (net (code "101") (name "/SLOT2.LVDS_11_P") (class "Default")
      (node (ref "IC4") (pin "AA24") (pinfunction "IO_L23P_T3_A03_D19_14_AA24") (pintype "bidirectional"))
    )
    (net (code "102") (name "/SLOT2.LVDS_12_N") (class "Default")
      (node (ref "IC4") (pin "AB29") (pinfunction "IO_L22N_T3_A04_D20_14_AB29") (pintype "bidirectional"))
    )
    (net (code "103") (name "/SLOT2.LVDS_12_P") (class "Default")
      (node (ref "IC4") (pin "AA29") (pinfunction "IO_L22P_T3_A05_D21_14_AA29") (pintype "bidirectional"))
    )
    (net (code "104") (name "/SLOT2.LVDS_13_N") (class "Default")
      (node (ref "IC4") (pin "Y33") (pinfunction "IO_L10N_T1_D15_14_Y33") (pintype "bidirectional"))
    )
    (net (code "105") (name "/SLOT2.LVDS_13_P") (class "Default")
      (node (ref "IC4") (pin "Y32") (pinfunction "IO_L10P_T1_D14_14_Y32") (pintype "bidirectional"))
    )
    (net (code "106") (name "/SLOT2.LVDS_14_N") (class "Default")
      (node (ref "IC4") (pin "Y31") (pinfunction "IO_L12N_T1_MRCC_14_Y31") (pintype "bidirectional"))
    )
    (net (code "107") (name "/SLOT2.LVDS_14_P") (class "Default")
      (node (ref "IC4") (pin "Y30") (pinfunction "IO_L12P_T1_MRCC_14_Y30") (pintype "bidirectional"))
    )
    (net (code "108") (name "/SLOT2.LVDS_15_N") (class "Default")
      (node (ref "IC4") (pin "AC32") (pinfunction "IO_L17N_T2_A13_D29_14_AC32") (pintype "bidirectional"))
    )
    (net (code "109") (name "/SLOT2.LVDS_15_P") (class "Default")
      (node (ref "IC4") (pin "AC31") (pinfunction "IO_L17P_T2_A14_D30_14_AC31") (pintype "bidirectional"))
    )
    (net (code "110") (name "/TxD_2V5") (class "Default")
      (node (ref "IC4") (pin "U9") (pinfunction "IO_L24P_T3_35_U9") (pintype "bidirectional"))
    )
    (net (code "114") (name "GND") (class "Default")
      (node (ref "R166") (pin "1") (pinfunction "1_1") (pintype "passive"))
      (node (ref "R167") (pin "1") (pinfunction "1_1") (pintype "passive"))
      (node (ref "R168") (pin "1") (pinfunction "1_1") (pintype "passive"))
      (node (ref "R169") (pin "1") (pinfunction "1_1") (pintype "passive"))
      (node (ref "R172") (pin "1") (pinfunction "1_1") (pintype "passive"))
      (node (ref "R173") (pin "1") (pinfunction "1_1") (pintype "passive"))
      (node (ref "R19") (pin "1") (pinfunction "1_1") (pintype "passive"))
      (node (ref "R227") (pin "1") (pinfunction "1_1") (pintype "passive"))
      (node (ref "R23") (pin "1") (pinfunction "1_1") (pintype "passive"))
      (node (ref "R43") (pin "1") (pinfunction "1_1") (pintype "passive"))
      (node (ref "R45") (pin "1") (pinfunction "1_1") (pintype "passive"))
      (node (ref "R9") (pin "1") (pinfunction "1_1") (pintype "passive"))
      (node (ref "SW1") (pin "2") (pinfunction "2_2") (pintype "bidirectional"))
      (node (ref "T12") (pin "2") (pinfunction "S_2") (pintype "passive"))
      (node (ref "T19") (pin "2") (pinfunction "S_2") (pintype "passive"))
      (node (ref "T2") (pin "2") (pinfunction "S_2") (pintype "passive"))
      (node (ref "T20") (pin "2") (pinfunction "S_2") (pintype "passive"))
      (node (ref "T3") (pin "2") (pinfunction "S_2") (pintype "passive"))
      (node (ref "TP28") (pin "1") (pinfunction "1_1") (pintype "bidirectional"))
      (node (ref "TP33") (pin "1") (pinfunction "1_1") (pintype "bidirectional"))
    )
    (net (code "115") (name "Net-(D17-A)") (class "Default")
      (node (ref "C159") (pin "1") (pinfunction "1_1") (pintype "passive"))
      (node (ref "D17") (pin "2") (pinfunction "A_2") (pintype "passive"))
      (node (ref "R150") (pin "1") (pinfunction "1_1") (pintype "passive"))
      (node (ref "T20") (pin "1") (pinfunction "G_1") (pintype "passive"))
    )
    (net (code "116") (name "Net-(D18-A)") (class "Default")
      (node (ref "D18") (pin "2") (pinfunction "A_2") (pintype "passive"))
      (node (ref "J21") (pin "1") (pinfunction "1_1") (pintype "bidirectional"))
      (node (ref "T20") (pin "3") (pinfunction "D_3") (pintype "passive"))
    )
    (net (code "117") (name "Net-(LD2-A)") (class "Default")
      (node (ref "LD2") (pin "2") (pinfunction "A_2") (pintype "passive"))
      (node (ref "R44") (pin "1") (pinfunction "1_1") (pintype "passive"))
    )
    (net (code "118") (name "Net-(LD2-C)") (class "Default")
      (node (ref "LD2") (pin "1") (pinfunction "C_1") (pintype "passive"))
      (node (ref "T3") (pin "3") (pinfunction "D_3") (pintype "passive"))
    )
    (net (code "119") (name "Net-(LD13-A)") (class "Default")
      (node (ref "LD13") (pin "2") (pinfunction "A_2") (pintype "passive"))
      (node (ref "R11") (pin "1") (pinfunction "1_1") (pintype "passive"))
    )
    (net (code "120") (name "Net-(LD13-C)") (class "Default")
      (node (ref "LD13") (pin "1") (pinfunction "C_1") (pintype "passive"))
      (node (ref "T2") (pin "3") (pinfunction "D_3") (pintype "passive"))
    )
    (net (code "121") (name "Net-(LD14-A)") (class "Default")
      (node (ref "LD14") (pin "2") (pinfunction "A_2") (pintype "passive"))
      (node (ref "R20") (pin "1") (pinfunction "1_1") (pintype "passive"))
    )
    (net (code "122") (name "Net-(LD14-C)") (class "Default")
      (node (ref "LD14") (pin "1") (pinfunction "C_1") (pintype "passive"))
      (node (ref "T12") (pin "3") (pinfunction "D_3") (pintype "passive"))
    )
    (net (code "123") (name "Net-(LD18-A)") (class "Default")
      (node (ref "LD18") (pin "2") (pinfunction "A_2") (pintype "passive"))
      (node (ref "R226") (pin "1") (pinfunction "1_1") (pintype "passive"))
    )
    (net (code "124") (name "Net-(LD18-C)") (class "Default")
      (node (ref "LD18") (pin "1") (pinfunction "C_1") (pintype "passive"))
      (node (ref "T19") (pin "3") (pinfunction "D_3") (pintype "passive"))
    )
    (net (code "125") (name "P2V5") (class "Default")
      (node (ref "D17") (pin "1") (pinfunction "C_1") (pintype "passive"))
      (node (ref "R150") (pin "2") (pinfunction "2_2") (pintype "passive"))
      (node (ref "R162") (pin "2") (pinfunction "2_2") (pintype "passive"))
      (node (ref "R163") (pin "2") (pinfunction "2_2") (pintype "passive"))
      (node (ref "R164") (pin "2") (pinfunction "2_2") (pintype "passive"))
      (node (ref "R165") (pin "2") (pinfunction "2_2") (pintype "passive"))
      (node (ref "R170") (pin "2") (pinfunction "2_2") (pintype "passive"))
      (node (ref "R171") (pin "2") (pinfunction "2_2") (pintype "passive"))
      (node (ref "R289") (pin "2") (pinfunction "2_2") (pintype "passive"))
      (node (ref "R42") (pin "2") (pinfunction "2_2") (pintype "passive"))
      (node (ref "TP32") (pin "1") (pinfunction "1_1") (pintype "bidirectional"))
    )
    (net (code "126") (name "P3V3") (class "Default")
      (node (ref "R11") (pin "2") (pinfunction "2_2") (pintype "passive"))
      (node (ref "R20") (pin "2") (pinfunction "2_2") (pintype "passive"))
      (node (ref "R226") (pin "2") (pinfunction "2_2") (pintype "passive"))
      (node (ref "R44") (pin "2") (pinfunction "2_2") (pintype "passive"))
      (node (ref "TP31") (pin "1") (pinfunction "1_1") (pintype "bidirectional"))
    )
    (net (code "127") (name "P12V0") (class "Default")
      (node (ref "D18") (pin "1") (pinfunction "C_1") (pintype "passive"))
      (node (ref "J21") (pin "2") (pinfunction "2_2") (pintype "bidirectional"))
    )
    (net (code "128") (name "unconnected-(IC4A-IO_0_12-PadAJ24)") (class "Default")
      (node (ref "IC4") (pin "AJ24") (pinfunction "IO_0_12_AJ24") (pintype "bidirectional+no_connect"))
    )
    (net (code "129") (name "unconnected-(IC4A-IO_25_12-PadAL24)") (class "Default")
      (node (ref "IC4") (pin "AL24") (pinfunction "IO_25_12_AL24") (pintype "bidirectional+no_connect"))
    )
    (net (code "130") (name "unconnected-(IC4A-IO_L9N_T1_DQS_12-PadAK31)") (class "Default")
      (node (ref "IC4") (pin "AK31") (pinfunction "IO_L9N_T1_DQS_12_AK31") (pintype "bidirectional+no_connect"))
    )
    (net (code "131") (name "unconnected-(IC4A-IO_L9P_T1_DQS_12-PadAJ30)") (class "Default")
      (node (ref "IC4") (pin "AJ30") (pinfunction "IO_L9P_T1_DQS_12_AJ30") (pintype "bidirectional+no_connect"))
    )
    (net (code "132") (name "unconnected-(IC4A-IO_L10N_T1_12-PadAP31)") (class "Default")
      (node (ref "IC4") (pin "AP31") (pinfunction "IO_L10N_T1_12_AP31") (pintype "bidirectional+no_connect"))
    )
    (net (code "133") (name "unconnected-(IC4A-IO_L10P_T1_12-PadAN31)") (class "Default")
      (node (ref "IC4") (pin "AN31") (pinfunction "IO_L10P_T1_12_AN31") (pintype "bidirectional+no_connect"))
    )
    (net (code "134") (name "unconnected-(IC4A-IO_L18N_T2_12-PadAL27)") (class "Default")
      (node (ref "IC4") (pin "AL27") (pinfunction "IO_L18N_T2_12_AL27") (pintype "bidirectional+no_connect"))
    )
    (net (code "135") (name "unconnected-(IC4A-IO_L18P_T2_12-PadAK27)") (class "Default")
      (node (ref "IC4") (pin "AK27") (pinfunction "IO_L18P_T2_12_AK27") (pintype "bidirectional+no_connect"))
    )
    (net (code "136") (name "unconnected-(IC4A-IO_L19N_T3_VREF_12-PadAK25)") (class "Default")
      (node (ref "IC4") (pin "AK25") (pinfunction "IO_L19N_T3_VREF_12_AK25") (pintype "bidirectional+no_connect"))
    )
    (net (code "137") (name "unconnected-(IC4A-IO_L19P_T3_12-PadAJ25)") (class "Default")
      (node (ref "IC4") (pin "AJ25") (pinfunction "IO_L19P_T3_12_AJ25") (pintype "bidirectional+no_connect"))
    )
    (net (code "138") (name "unconnected-(IC4A-IO_L20N_T3_12-PadAK26)") (class "Default")
      (node (ref "IC4") (pin "AK26") (pinfunction "IO_L20N_T3_12_AK26") (pintype "bidirectional+no_connect"))
    )
    (net (code "139") (name "unconnected-(IC4A-IO_L20P_T3_12-PadAJ26)") (class "Default")
      (node (ref "IC4") (pin "AJ26") (pinfunction "IO_L20P_T3_12_AJ26") (pintype "bidirectional+no_connect"))
    )
    (net (code "140") (name "unconnected-(IC4A-IO_L21N_T3_DQS_12-PadAN26)") (class "Default")
      (node (ref "IC4") (pin "AN26") (pinfunction "IO_L21N_T3_DQS_12_AN26") (pintype "bidirectional+no_connect"))
    )
    (net (code "141") (name "unconnected-(IC4A-IO_L21P_T3_DQS_12-PadAM26)") (class "Default")
      (node (ref "IC4") (pin "AM26") (pinfunction "IO_L21P_T3_DQS_12_AM26") (pintype "bidirectional+no_connect"))
    )
    (net (code "142") (name "unconnected-(IC4A-IO_L23N_T3_12-PadAM25)") (class "Default")
      (node (ref "IC4") (pin "AM25") (pinfunction "IO_L23N_T3_12_AM25") (pintype "bidirectional+no_connect"))
    )
    (net (code "143") (name "unconnected-(IC4A-IO_L23P_T3_12-PadAL25)") (class "Default")
      (node (ref "IC4") (pin "AL25") (pinfunction "IO_L23P_T3_12_AL25") (pintype "bidirectional+no_connect"))
    )
    (net (code "144") (name "unconnected-(IC4A-IO_L24N_T3_12-PadAP26)") (class "Default")
      (node (ref "IC4") (pin "AP26") (pinfunction "IO_L24N_T3_12_AP26") (pintype "bidirectional+no_connect"))
    )
    (net (code "145") (name "unconnected-(IC4A-IO_L24P_T3_12-PadAP25)") (class "Default")
      (node (ref "IC4") (pin "AP25") (pinfunction "IO_L24P_T3_12_AP25") (pintype "bidirectional+no_connect"))
    )
    (net (code "146") (name "unconnected-(IC4C-IO_0_14-PadV24)") (class "Default")
      (node (ref "IC4") (pin "V24") (pinfunction "IO_0_14_V24") (pintype "bidirectional+no_connect"))
    )
    (net (code "147") (name "unconnected-(IC4C-IO_25_14-PadW24)") (class "Default")
      (node (ref "IC4") (pin "W24") (pinfunction "IO_25_14_W24") (pintype "bidirectional+no_connect"))
    )
    (net (code "148") (name "unconnected-(IC4C-IO_L3N_T0_DQS_EMCCLK_14-PadY26)") (class "Default")
      (node (ref "IC4") (pin "Y26") (pinfunction "IO_L3N_T0_DQS_EMCCLK_14_Y26") (pintype "bidirectional+no_connect"))
    )
    (net (code "149") (name "unconnected-(IC4C-IO_L4N_T0_D05_14-PadW29)") (class "Default")
      (node (ref "IC4") (pin "W29") (pinfunction "IO_L4N_T0_D05_14_W29") (pintype "bidirectional+no_connect"))
    )
    (net (code "150") (name "unconnected-(IC4C-IO_L4P_T0_D04_14-PadW28)") (class "Default")
      (node (ref "IC4") (pin "W28") (pinfunction "IO_L4P_T0_D04_14_W28") (pintype "bidirectional+no_connect"))
    )
    (net (code "151") (name "unconnected-(IC4C-IO_L5N_T0_D07_14-PadY25)") (class "Default")
      (node (ref "IC4") (pin "Y25") (pinfunction "IO_L5N_T0_D07_14_Y25") (pintype "bidirectional+no_connect"))
    )
    (net (code "152") (name "unconnected-(IC4C-IO_L5P_T0_D06_14-PadW25)") (class "Default")
      (node (ref "IC4") (pin "W25") (pinfunction "IO_L5P_T0_D06_14_W25") (pintype "bidirectional+no_connect"))
    )
    (net (code "153") (name "unconnected-(IC4C-IO_L6N_T0_D08_VREF_14-PadY28)") (class "Default")
      (node (ref "IC4") (pin "Y28") (pinfunction "IO_L6N_T0_D08_VREF_14_Y28") (pintype "bidirectional+no_connect"))
    )
    (net (code "154") (name "unconnected-(IC4C-IO_L6P_T0_FCS_B_14-PadY27)") (class "Default")
      (node (ref "IC4") (pin "Y27") (pinfunction "IO_L6P_T0_FCS_B_14_Y27") (pintype "bidirectional+no_connect"))
    )
    (net (code "155") (name "unconnected-(IC4C-IO_L7N_T1_D10_14-PadV32)") (class "Default")
      (node (ref "IC4") (pin "V32") (pinfunction "IO_L7N_T1_D10_14_V32") (pintype "bidirectional+no_connect"))
    )
    (net (code "156") (name "unconnected-(IC4C-IO_L7P_T1_D09_14-PadV31)") (class "Default")
      (node (ref "IC4") (pin "V31") (pinfunction "IO_L7P_T1_D09_14_V31") (pintype "bidirectional+no_connect"))
    )
    (net (code "157") (name "unconnected-(IC4C-IO_L9N_T1_DQS_D13_14-PadV34)") (class "Default")
      (node (ref "IC4") (pin "V34") (pinfunction "IO_L9N_T1_DQS_D13_14_V34") (pintype "bidirectional+no_connect"))
    )
    (net (code "158") (name "unconnected-(IC4C-IO_L9P_T1_DQS_14-PadV33)") (class "Default")
      (node (ref "IC4") (pin "V33") (pinfunction "IO_L9P_T1_DQS_14_V33") (pintype "bidirectional+no_connect"))
    )
    (net (code "159") (name "unconnected-(IC4I-IO_0_35-PadR11)") (class "Default")
      (node (ref "IC4") (pin "R11") (pinfunction "IO_0_35_R11") (pintype "bidirectional+no_connect"))
    )
    (net (code "160") (name "unconnected-(IC4I-IO_L1N_T0_AD4N_35-PadM6)") (class "Default")
      (node (ref "IC4") (pin "M6") (pinfunction "IO_L1N_T0_AD4N_35_M6") (pintype "bidirectional+no_connect"))
    )
    (net (code "161") (name "unconnected-(IC4I-IO_L1P_T0_AD4P_35-PadM7)") (class "Default")
      (node (ref "IC4") (pin "M7") (pinfunction "IO_L1P_T0_AD4P_35_M7") (pintype "bidirectional+no_connect"))
    )
    (net (code "162") (name "unconnected-(IC4I-IO_L2N_T0_AD12N_35-PadM9)") (class "Default")
      (node (ref "IC4") (pin "M9") (pinfunction "IO_L2N_T0_AD12N_35_M9") (pintype "bidirectional+no_connect"))
    )
    (net (code "163") (name "unconnected-(IC4I-IO_L5P_T0_AD13P_35-PadP9)") (class "Default")
      (node (ref "IC4") (pin "P9") (pinfunction "IO_L5P_T0_AD13P_35_P9") (pintype "bidirectional+no_connect"))
    )
    (net (code "164") (name "unconnected-(IC4I-IO_L8N_T1_AD14N_35-PadM4)") (class "Default")
      (node (ref "IC4") (pin "M4") (pinfunction "IO_L8N_T1_AD14N_35_M4") (pintype "bidirectional+no_connect"))
    )
    (net (code "165") (name "unconnected-(IC4I-IO_L8P_T1_AD14P_35-PadM5)") (class "Default")
      (node (ref "IC4") (pin "M5") (pinfunction "IO_L8P_T1_AD14P_35_M5") (pintype "bidirectional+no_connect"))
    )
    (net (code "166") (name "unconnected-(IC4I-IO_L10P_T1_AD15P_35-PadN3)") (class "Default")
      (node (ref "IC4") (pin "N3") (pinfunction "IO_L10P_T1_AD15P_35_N3") (pintype "bidirectional+no_connect"))
    )
    (net (code "167") (name "unconnected-(IC4I-IO_L14N_T2_SRCC_35-PadT4)") (class "Default")
      (node (ref "IC4") (pin "T4") (pinfunction "IO_L14N_T2_SRCC_35_T4") (pintype "bidirectional+no_connect"))
    )
    (net (code "168") (name "unconnected-(IC4I-IO_L14P_T2_SRCC_35-PadT5)") (class "Default")
      (node (ref "IC4") (pin "T5") (pinfunction "IO_L14P_T2_SRCC_35_T5") (pintype "bidirectional+no_connect"))
    )
    (net (code "169") (name "unconnected-(IC4I-IO_L15P_T2_DQS_35-PadR3)") (class "Default")
      (node (ref "IC4") (pin "R3") (pinfunction "IO_L15P_T2_DQS_35_R3") (pintype "bidirectional+no_connect"))
    )
    (net (code "170") (name "unconnected-(IC4I-IO_L16P_T2_35-PadU2)") (class "Default")
      (node (ref "IC4") (pin "U2") (pinfunction "IO_L16P_T2_35_U2") (pintype "bidirectional+no_connect"))
    )
    (net (code "171") (name "unconnected-(IC4I-IO_L17N_T2_35-PadT2)") (class "Default")
      (node (ref "IC4") (pin "T2") (pinfunction "IO_L17N_T2_35_T2") (pintype "bidirectional"))
    )
    (net (code "172") (name "unconnected-(IC4I-IO_L17P_T2_35-PadT3)") (class "Default")
      (node (ref "IC4") (pin "T3") (pinfunction "IO_L17P_T2_35_T3") (pintype "bidirectional+no_connect"))
    )
    (net (code "173") (name "unconnected-(IC4I-IO_L19N_T3_VREF_35-PadR7)") (class "Default")
      (node (ref "IC4") (pin "R7") (pinfunction "IO_L19N_T3_VREF_35_R7") (pintype "bidirectional+no_connect"))
    )
    (net (code "174") (name "unconnected-(IC4I-IO_L22P_T3_35-PadU7)") (class "Default")
      (node (ref "IC4") (pin "U7") (pinfunction "IO_L22P_T3_35_U7") (pintype "bidirectional+no_connect"))
    )
  )
)
